# pressure_adc.net
KiCad netlist of a schematic drawn in Altium Designer
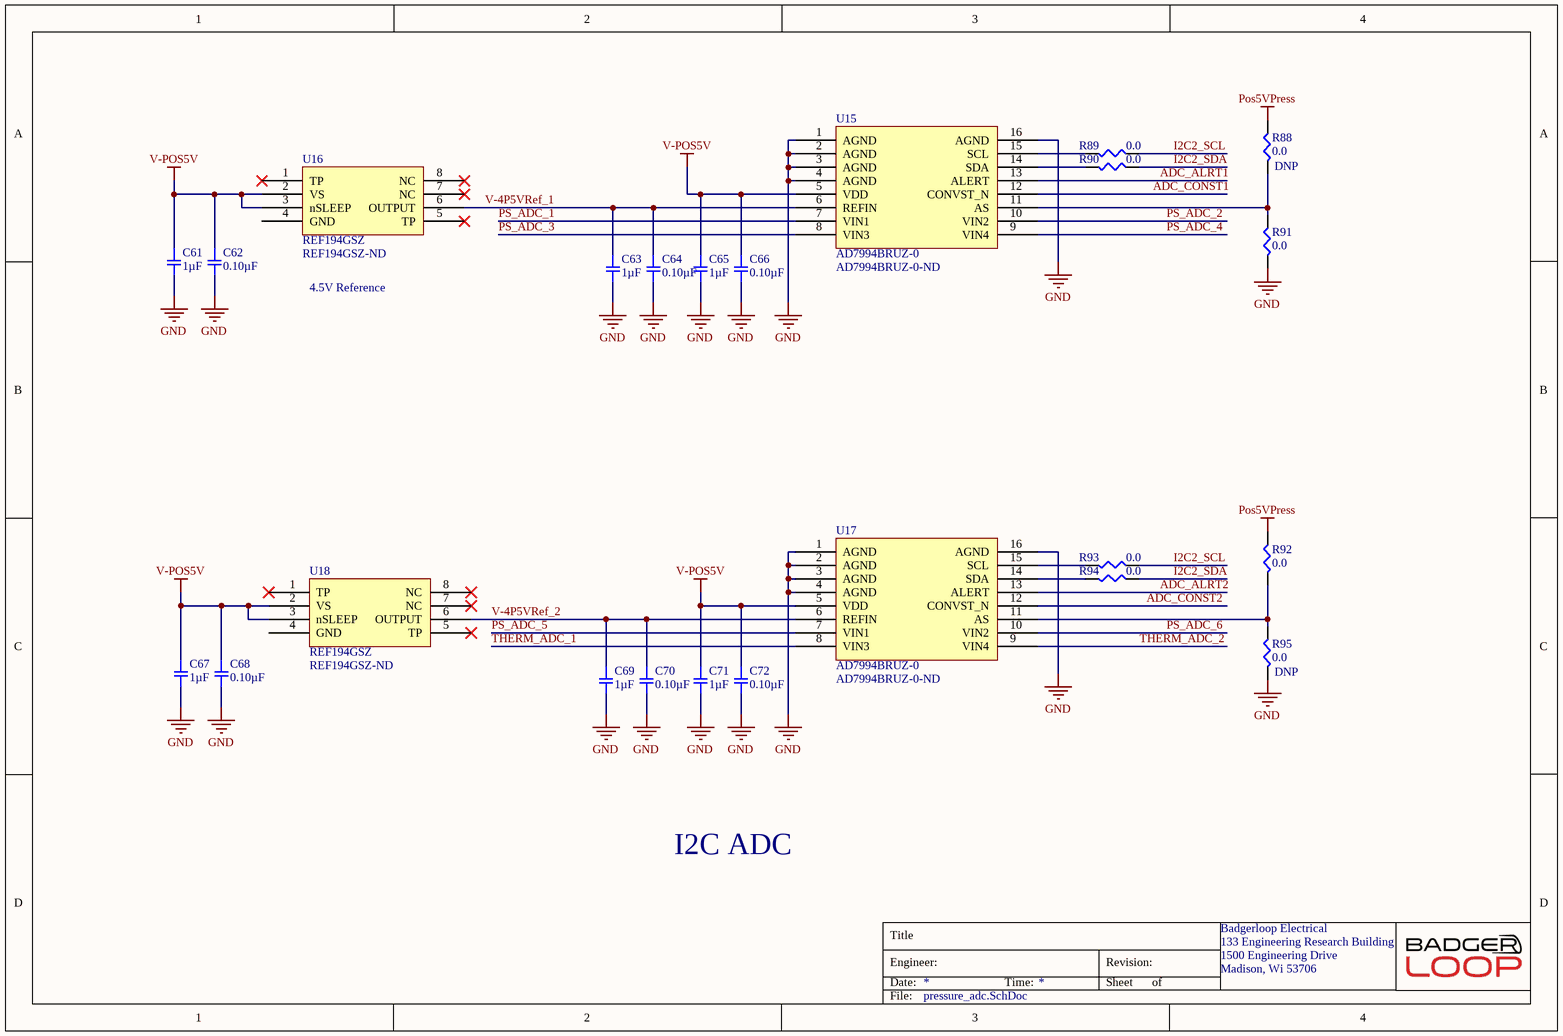
[diagram p0: pressure_adc.SchDoc]

(export (version "E")
  (design (tool "Eeschema 10.0.6"))
  (components
    (comp (ref "C61")
      (value "1µF")
      (footprint "SMD-0805C")
      (description "CAP CER 1UF 50V X7R 0805")
      (fields
        (field (name "DIGI-KEY PART NUMBER") "490-4736-1-ND")
        (field (name "PART NUMBER") "GRM21BR71H105KA12L")
      )
      (libsource (lib "capacitors") (part "GRM21BR71H105KA12L"))
    )
    (comp (ref "C62")
      (value "0.10µF")
      (footprint "SMD-0805C")
      (description "CAP CER 0.1UF 50V X7R 0805")
      (fields
        (field (name "DIGI-KEY PART NUMBER") "490-11955-1-ND")
        (field (name "PART NUMBER") "GCD21BR71H104KA01L")
      )
      (libsource (lib "capacitors") (part "GCD21BR71H104KA01L"))
    )
    (comp (ref "C63")
      (value "1µF")
      (footprint "SMD-0805C")
      (description "CAP CER 1UF 50V X7R 0805")
      (fields
        (field (name "DIGI-KEY PART NUMBER") "490-4736-1-ND")
        (field (name "PART NUMBER") "GRM21BR71H105KA12L")
      )
      (libsource (lib "capacitors") (part "GRM21BR71H105KA12L"))
    )
    (comp (ref "C64")
      (value "0.10µF")
      (footprint "SMD-0805C")
      (description "CAP CER 0.1UF 50V X7R 0805")
      (fields
        (field (name "DIGI-KEY PART NUMBER") "490-11955-1-ND")
        (field (name "PART NUMBER") "GCD21BR71H104KA01L")
      )
      (libsource (lib "capacitors") (part "GCD21BR71H104KA01L"))
    )
    (comp (ref "C65")
      (value "1µF")
      (footprint "SMD-0805C")
      (description "CAP CER 1UF 50V X7R 0805")
      (fields
        (field (name "DIGI-KEY PART NUMBER") "490-4736-1-ND")
        (field (name "PART NUMBER") "GRM21BR71H105KA12L")
      )
      (libsource (lib "capacitors") (part "GRM21BR71H105KA12L"))
    )
    (comp (ref "C66")
      (value "0.10µF")
      (footprint "SMD-0805C")
      (description "CAP CER 0.1UF 50V X7R 0805")
      (fields
        (field (name "DIGI-KEY PART NUMBER") "490-11955-1-ND")
        (field (name "PART NUMBER") "GCD21BR71H104KA01L")
      )
      (libsource (lib "capacitors") (part "GCD21BR71H104KA01L"))
    )
    (comp (ref "C67")
      (value "1µF")
      (footprint "SMD-0805C")
      (description "CAP CER 1UF 50V X7R 0805")
      (fields
        (field (name "DIGI-KEY PART NUMBER") "490-4736-1-ND")
        (field (name "PART NUMBER") "GRM21BR71H105KA12L")
      )
      (libsource (lib "capacitors") (part "GRM21BR71H105KA12L"))
    )
    (comp (ref "C68")
      (value "0.10µF")
      (footprint "SMD-0805C")
      (description "CAP CER 0.1UF 50V X7R 0805")
      (fields
        (field (name "DIGI-KEY PART NUMBER") "490-11955-1-ND")
        (field (name "PART NUMBER") "GCD21BR71H104KA01L")
      )
      (libsource (lib "capacitors") (part "GCD21BR71H104KA01L"))
    )
    (comp (ref "C69")
      (value "1µF")
      (footprint "SMD-0805C")
      (description "CAP CER 1UF 50V X7R 0805")
      (fields
        (field (name "DIGI-KEY PART NUMBER") "490-4736-1-ND")
        (field (name "PART NUMBER") "GRM21BR71H105KA12L")
      )
      (libsource (lib "capacitors") (part "GRM21BR71H105KA12L"))
    )
    (comp (ref "C70")
      (value "0.10µF")
      (footprint "SMD-0805C")
      (description "CAP CER 0.1UF 50V X7R 0805")
      (fields
        (field (name "DIGI-KEY PART NUMBER") "490-11955-1-ND")
        (field (name "PART NUMBER") "GCD21BR71H104KA01L")
      )
      (libsource (lib "capacitors") (part "GCD21BR71H104KA01L"))
    )
    (comp (ref "C71")
      (value "1µF")
      (footprint "SMD-0805C")
      (description "CAP CER 1UF 50V X7R 0805")
      (fields
        (field (name "DIGI-KEY PART NUMBER") "490-4736-1-ND")
        (field (name "PART NUMBER") "GRM21BR71H105KA12L")
      )
      (libsource (lib "capacitors") (part "GRM21BR71H105KA12L"))
    )
    (comp (ref "C72")
      (value "0.10µF")
      (footprint "SMD-0805C")
      (description "CAP CER 0.1UF 50V X7R 0805")
      (fields
        (field (name "DIGI-KEY PART NUMBER") "490-11955-1-ND")
        (field (name "PART NUMBER") "GCD21BR71H104KA01L")
      )
      (libsource (lib "capacitors") (part "GCD21BR71H104KA01L"))
    )
    (comp (ref "R88")
      (value "0.0")
      (footprint "SMD-0805-RES")
      (description "RES SMD 0.0 OHM JUMPER 1/8W 0805")
      (fields
        (field (name "PART NUMBER") "ERJ-6GEY0R00V")
        (field (name "DIGI-KEY PART NUMBER") "P0.0ACT-ND")
        (field (name "DNP") "DNP")
      )
      (libsource (lib "resistors") (part "ERJ-6GEY0R00V"))
    )
    (comp (ref "R89")
      (value "0.0")
      (footprint "SMD-0805-RES")
      (description "RES SMD 0.0 OHM JUMPER 1/8W 0805")
      (fields (field (name "PART NUMBER") "ERJ-6GEY0R00V") (field (name "DIGI-KEY PART NUMBER") "P0.0ACT-ND"))
      (libsource (lib "resistors") (part "ERJ-6GEY0R00V"))
    )
    (comp (ref "R90")
      (value "0.0")
      (footprint "SMD-0805-RES")
      (description "RES SMD 0.0 OHM JUMPER 1/8W 0805")
      (fields (field (name "PART NUMBER") "ERJ-6GEY0R00V") (field (name "DIGI-KEY PART NUMBER") "P0.0ACT-ND"))
      (libsource (lib "resistors") (part "ERJ-6GEY0R00V"))
    )
    (comp (ref "R91")
      (value "0.0")
      (footprint "SMD-0805-RES")
      (description "RES SMD 0.0 OHM JUMPER 1/8W 0805")
      (fields (field (name "PART NUMBER") "ERJ-6GEY0R00V") (field (name "DIGI-KEY PART NUMBER") "P0.0ACT-ND"))
      (libsource (lib "resistors") (part "ERJ-6GEY0R00V"))
    )
    (comp (ref "R92")
      (value "0.0")
      (footprint "SMD-0805-RES")
      (description "RES SMD 0.0 OHM JUMPER 1/8W 0805")
      (fields (field (name "PART NUMBER") "ERJ-6GEY0R00V") (field (name "DIGI-KEY PART NUMBER") "P0.0ACT-ND"))
      (libsource (lib "resistors") (part "ERJ-6GEY0R00V"))
    )
    (comp (ref "R93")
      (value "0.0")
      (footprint "SMD-0805-RES")
      (description "RES SMD 0.0 OHM JUMPER 1/8W 0805")
      (fields (field (name "PART NUMBER") "ERJ-6GEY0R00V") (field (name "DIGI-KEY PART NUMBER") "P0.0ACT-ND"))
      (libsource (lib "resistors") (part "ERJ-6GEY0R00V"))
    )
    (comp (ref "R94")
      (value "0.0")
      (footprint "SMD-0805-RES")
      (description "RES SMD 0.0 OHM JUMPER 1/8W 0805")
      (fields (field (name "PART NUMBER") "ERJ-6GEY0R00V") (field (name "DIGI-KEY PART NUMBER") "P0.0ACT-ND"))
      (libsource (lib "resistors") (part "ERJ-6GEY0R00V"))
    )
    (comp (ref "R95")
      (value "0.0")
      (footprint "SMD-0805-RES")
      (description "RES SMD 0.0 OHM JUMPER 1/8W 0805")
      (fields
        (field (name "PART NUMBER") "ERJ-6GEY0R00V")
        (field (name "DIGI-KEY PART NUMBER") "P0.0ACT-ND")
        (field (name "DNP") "DNP")
      )
      (libsource (lib "resistors") (part "ERJ-6GEY0R00V"))
    )
    (comp (ref "U15")
      (value "AD7994BRUZ-0")
      (description "ANALOG DEVICES - AD7994BRUZ-0 - 12BIT ADC, 4CH I2C I/F, SMD, 7994")
      (fields
        (field (name "MANUFACTURER") "Analog Devices")
        (field (name "SUPPLIER PART NUMBER 1") "AD7994BRUZ-0-ND")
      )
      (libsource (lib "ic") (part "AD7994BRUZ-0"))
    )
    (comp (ref "U16")
      (value "REF194GSZ")
      (footprint "SOP127P600X175-8N")
      (description "IC VREF SERIES 4.5V 8SOIC")
      (fields
        (field (name "MANUFACTURER") "Analog Devices")
        (field (name "SUPPLIER PART NUMBER 1") "REF194GSZ-ND")
      )
      (libsource (lib "ic") (part "REF194GSZ"))
    )
    (comp (ref "U17")
      (value "AD7994BRUZ-0")
      (description "ANALOG DEVICES - AD7994BRUZ-0 - 12BIT ADC, 4CH I2C I/F, SMD, 7994")
      (fields
        (field (name "MANUFACTURER") "Analog Devices")
        (field (name "SUPPLIER PART NUMBER 1") "AD7994BRUZ-0-ND")
      )
      (libsource (lib "ic") (part "AD7994BRUZ-0"))
    )
    (comp (ref "U18")
      (value "REF194GSZ")
      (footprint "SOP127P600X175-8N")
      (description "IC VREF SERIES 4.5V 8SOIC")
      (fields
        (field (name "MANUFACTURER") "Analog Devices")
        (field (name "SUPPLIER PART NUMBER 1") "REF194GSZ-ND")
      )
      (libsource (lib "ic") (part "REF194GSZ"))
    )
  )
  (nets
    (net (code "1") (name "/ADC_ALRT1") (class "Default")
      (node (ref "U15") (pin "13") (pinfunction "ALERT_13") (pintype "passive"))
    )
    (net (code "2") (name "/ADC_ALRT2") (class "Default")
      (node (ref "U17") (pin "13") (pinfunction "ALERT_13") (pintype "passive"))
    )
    (net (code "3") (name "/ADC_CONST1") (class "Default")
      (node (ref "U15") (pin "12") (pinfunction "CONVST_N_12") (pintype "passive"))
    )
    (net (code "4") (name "/ADC_CONST2") (class "Default")
      (node (ref "U17") (pin "12") (pinfunction "CONVST_N_12") (pintype "passive"))
    )
    (net (code "5") (name "/I2C2_SCL") (class "Default")
      (node (ref "R89") (pin "1") (pinfunction "1_1") (pintype "passive"))
      (node (ref "R93") (pin "1") (pinfunction "1_1") (pintype "passive"))
    )
    (net (code "6") (name "/I2C2_SDA") (class "Default")
      (node (ref "R90") (pin "1") (pinfunction "1_1") (pintype "passive"))
      (node (ref "R94") (pin "1") (pinfunction "1_1") (pintype "passive"))
    )
    (net (code "7") (name "/PS_ADC_1") (class "Default")
      (node (ref "U15") (pin "7") (pinfunction "VIN1_7") (pintype "passive"))
    )
    (net (code "8") (name "/PS_ADC_2") (class "Default")
      (node (ref "U15") (pin "10") (pinfunction "VIN2_10") (pintype "passive"))
    )
    (net (code "9") (name "/PS_ADC_3") (class "Default")
      (node (ref "U15") (pin "8") (pinfunction "VIN3_8") (pintype "passive"))
    )
    (net (code "10") (name "/PS_ADC_4") (class "Default")
      (node (ref "U15") (pin "9") (pinfunction "VIN4_9") (pintype "passive"))
    )
    (net (code "11") (name "/PS_ADC_5") (class "Default")
      (node (ref "U17") (pin "7") (pinfunction "VIN1_7") (pintype "passive"))
    )
    (net (code "12") (name "/PS_ADC_6") (class "Default")
      (node (ref "U17") (pin "10") (pinfunction "VIN2_10") (pintype "passive"))
    )
    (net (code "13") (name "/THERM_ADC_1") (class "Default")
      (node (ref "U17") (pin "8") (pinfunction "VIN3_8") (pintype "passive"))
    )
    (net (code "14") (name "/THERM_ADC_2") (class "Default")
      (node (ref "U17") (pin "9") (pinfunction "VIN4_9") (pintype "passive"))
    )
    (net (code "15") (name "/V-4P5VRef_1") (class "Default")
      (node (ref "C63") (pin "1") (pinfunction "1_1") (pintype "passive"))
      (node (ref "C64") (pin "1") (pinfunction "1_1") (pintype "passive"))
      (node (ref "U15") (pin "6") (pinfunction "REFIN_6") (pintype "passive"))
      (node (ref "U16") (pin "6") (pinfunction "OUTPUT_6") (pintype "passive"))
    )
    (net (code "16") (name "/V-4P5VRef_2") (class "Default")
      (node (ref "C69") (pin "1") (pinfunction "1_1") (pintype "passive"))
      (node (ref "C70") (pin "1") (pinfunction "1_1") (pintype "passive"))
      (node (ref "U17") (pin "6") (pinfunction "REFIN_6") (pintype "passive"))
      (node (ref "U18") (pin "6") (pinfunction "OUTPUT_6") (pintype "passive"))
    )
    (net (code "17") (name "GND") (class "Default")
      (node (ref "C61") (pin "2") (pinfunction "2_2") (pintype "passive"))
      (node (ref "C62") (pin "2") (pinfunction "2_2") (pintype "passive"))
      (node (ref "C63") (pin "2") (pinfunction "2_2") (pintype "passive"))
      (node (ref "C64") (pin "2") (pinfunction "2_2") (pintype "passive"))
      (node (ref "C65") (pin "2") (pinfunction "2_2") (pintype "passive"))
      (node (ref "C66") (pin "2") (pinfunction "2_2") (pintype "passive"))
      (node (ref "C67") (pin "2") (pinfunction "2_2") (pintype "passive"))
      (node (ref "C68") (pin "2") (pinfunction "2_2") (pintype "passive"))
      (node (ref "C69") (pin "2") (pinfunction "2_2") (pintype "passive"))
      (node (ref "C70") (pin "2") (pinfunction "2_2") (pintype "passive"))
      (node (ref "C71") (pin "2") (pinfunction "2_2") (pintype "passive"))
      (node (ref "C72") (pin "2") (pinfunction "2_2") (pintype "passive"))
      (node (ref "R91") (pin "2") (pinfunction "2_2") (pintype "passive"))
      (node (ref "R95") (pin "2") (pinfunction "2_2") (pintype "passive"))
      (node (ref "U15") (pin "1") (pinfunction "AGND_1") (pintype "passive"))
      (node (ref "U15") (pin "16") (pinfunction "AGND_16") (pintype "passive"))
      (node (ref "U15") (pin "2") (pinfunction "AGND_2") (pintype "passive"))
      (node (ref "U15") (pin "3") (pinfunction "AGND_3") (pintype "passive"))
      (node (ref "U15") (pin "4") (pinfunction "AGND_4") (pintype "passive"))
      (node (ref "U17") (pin "1") (pinfunction "AGND_1") (pintype "passive"))
      (node (ref "U17") (pin "16") (pinfunction "AGND_16") (pintype "passive"))
      (node (ref "U17") (pin "2") (pinfunction "AGND_2") (pintype "passive"))
      (node (ref "U17") (pin "3") (pinfunction "AGND_3") (pintype "passive"))
      (node (ref "U17") (pin "4") (pinfunction "AGND_4") (pintype "passive"))
    )
    (net (code "18") (name "Net-(U15-AS)") (class "Default")
      (node (ref "R88") (pin "2") (pinfunction "2_2") (pintype "passive"))
      (node (ref "R91") (pin "1") (pinfunction "1_1") (pintype "passive"))
      (node (ref "U15") (pin "11") (pinfunction "AS_11") (pintype "passive"))
    )
    (net (code "19") (name "Net-(U15-SCL)") (class "Default")
      (node (ref "R89") (pin "2") (pinfunction "2_2") (pintype "passive"))
      (node (ref "U15") (pin "15") (pinfunction "SCL_15") (pintype "passive"))
    )
    (net (code "20") (name "Net-(U15-SDA)") (class "Default")
      (node (ref "R90") (pin "2") (pinfunction "2_2") (pintype "passive"))
      (node (ref "U15") (pin "14") (pinfunction "SDA_14") (pintype "passive"))
    )
    (net (code "21") (name "Net-(U17-AS)") (class "Default")
      (node (ref "R92") (pin "2") (pinfunction "2_2") (pintype "passive"))
      (node (ref "R95") (pin "1") (pinfunction "1_1") (pintype "passive"))
      (node (ref "U17") (pin "11") (pinfunction "AS_11") (pintype "passive"))
    )
    (net (code "22") (name "Net-(U17-SCL)") (class "Default")
      (node (ref "R93") (pin "2") (pinfunction "2_2") (pintype "passive"))
      (node (ref "U17") (pin "15") (pinfunction "SCL_15") (pintype "passive"))
    )
    (net (code "23") (name "Net-(U17-SDA)") (class "Default")
      (node (ref "R94") (pin "2") (pinfunction "2_2") (pintype "passive"))
      (node (ref "U17") (pin "14") (pinfunction "SDA_14") (pintype "passive"))
    )
    (net (code "24") (name "Pos5VPress") (class "Default")
      (node (ref "R88") (pin "1") (pinfunction "1_1") (pintype "passive"))
      (node (ref "R92") (pin "1") (pinfunction "1_1") (pintype "passive"))
    )
    (net (code "25") (name "V-POS5V") (class "Default")
      (node (ref "C61") (pin "1") (pinfunction "1_1") (pintype "passive"))
      (node (ref "C62") (pin "1") (pinfunction "1_1") (pintype "passive"))
      (node (ref "C65") (pin "1") (pinfunction "1_1") (pintype "passive"))
      (node (ref "C66") (pin "1") (pinfunction "1_1") (pintype "passive"))
      (node (ref "C67") (pin "1") (pinfunction "1_1") (pintype "passive"))
      (node (ref "C68") (pin "1") (pinfunction "1_1") (pintype "passive"))
      (node (ref "C71") (pin "1") (pinfunction "1_1") (pintype "passive"))
      (node (ref "C72") (pin "1") (pinfunction "1_1") (pintype "passive"))
      (node (ref "U15") (pin "5") (pinfunction "VDD_5") (pintype "passive"))
      (node (ref "U16") (pin "2") (pinfunction "VS_2") (pintype "passive"))
      (node (ref "U16") (pin "3") (pinfunction "nSLEEP_3") (pintype "passive"))
      (node (ref "U17") (pin "5") (pinfunction "VDD_5") (pintype "passive"))
      (node (ref "U18") (pin "2") (pinfunction "VS_2") (pintype "passive"))
      (node (ref "U18") (pin "3") (pinfunction "nSLEEP_3") (pintype "passive"))
    )
    (net (code "26") (name "unconnected-(U16-GND-Pad4)") (class "Default")
      (node (ref "U16") (pin "4") (pinfunction "GND_4") (pintype "passive"))
    )
    (net (code "27") (name "unconnected-(U16-NC-Pad7)") (class "Default")
      (node (ref "U16") (pin "7") (pinfunction "NC_7") (pintype "passive+no_connect"))
    )
    (net (code "28") (name "unconnected-(U16-NC-Pad8)") (class "Default")
      (node (ref "U16") (pin "8") (pinfunction "NC_8") (pintype "passive+no_connect"))
    )
    (net (code "29") (name "unconnected-(U16-TP-Pad1)") (class "Default")
      (node (ref "U16") (pin "1") (pinfunction "TP_1") (pintype "passive+no_connect"))
    )
    (net (code "30") (name "unconnected-(U16-TP-Pad5)") (class "Default")
      (node (ref "U16") (pin "5") (pinfunction "TP_5") (pintype "passive+no_connect"))
    )
    (net (code "31") (name "unconnected-(U18-GND-Pad4)") (class "Default")
      (node (ref "U18") (pin "4") (pinfunction "GND_4") (pintype "passive"))
    )
    (net (code "32") (name "unconnected-(U18-NC-Pad7)") (class "Default")
      (node (ref "U18") (pin "7") (pinfunction "NC_7") (pintype "passive+no_connect"))
    )
    (net (code "33") (name "unconnected-(U18-NC-Pad8)") (class "Default")
      (node (ref "U18") (pin "8") (pinfunction "NC_8") (pintype "passive+no_connect"))
    )
    (net (code "34") (name "unconnected-(U18-TP-Pad1)") (class "Default")
      (node (ref "U18") (pin "1") (pinfunction "TP_1") (pintype "passive+no_connect"))
    )
    (net (code "35") (name "unconnected-(U18-TP-Pad5)") (class "Default")
      (node (ref "U18") (pin "5") (pinfunction "TP_5") (pintype "passive+no_connect"))
    )
  )
)
